# divchrono-master.net
KiCad netlist of a schematic drawn in EAGLE
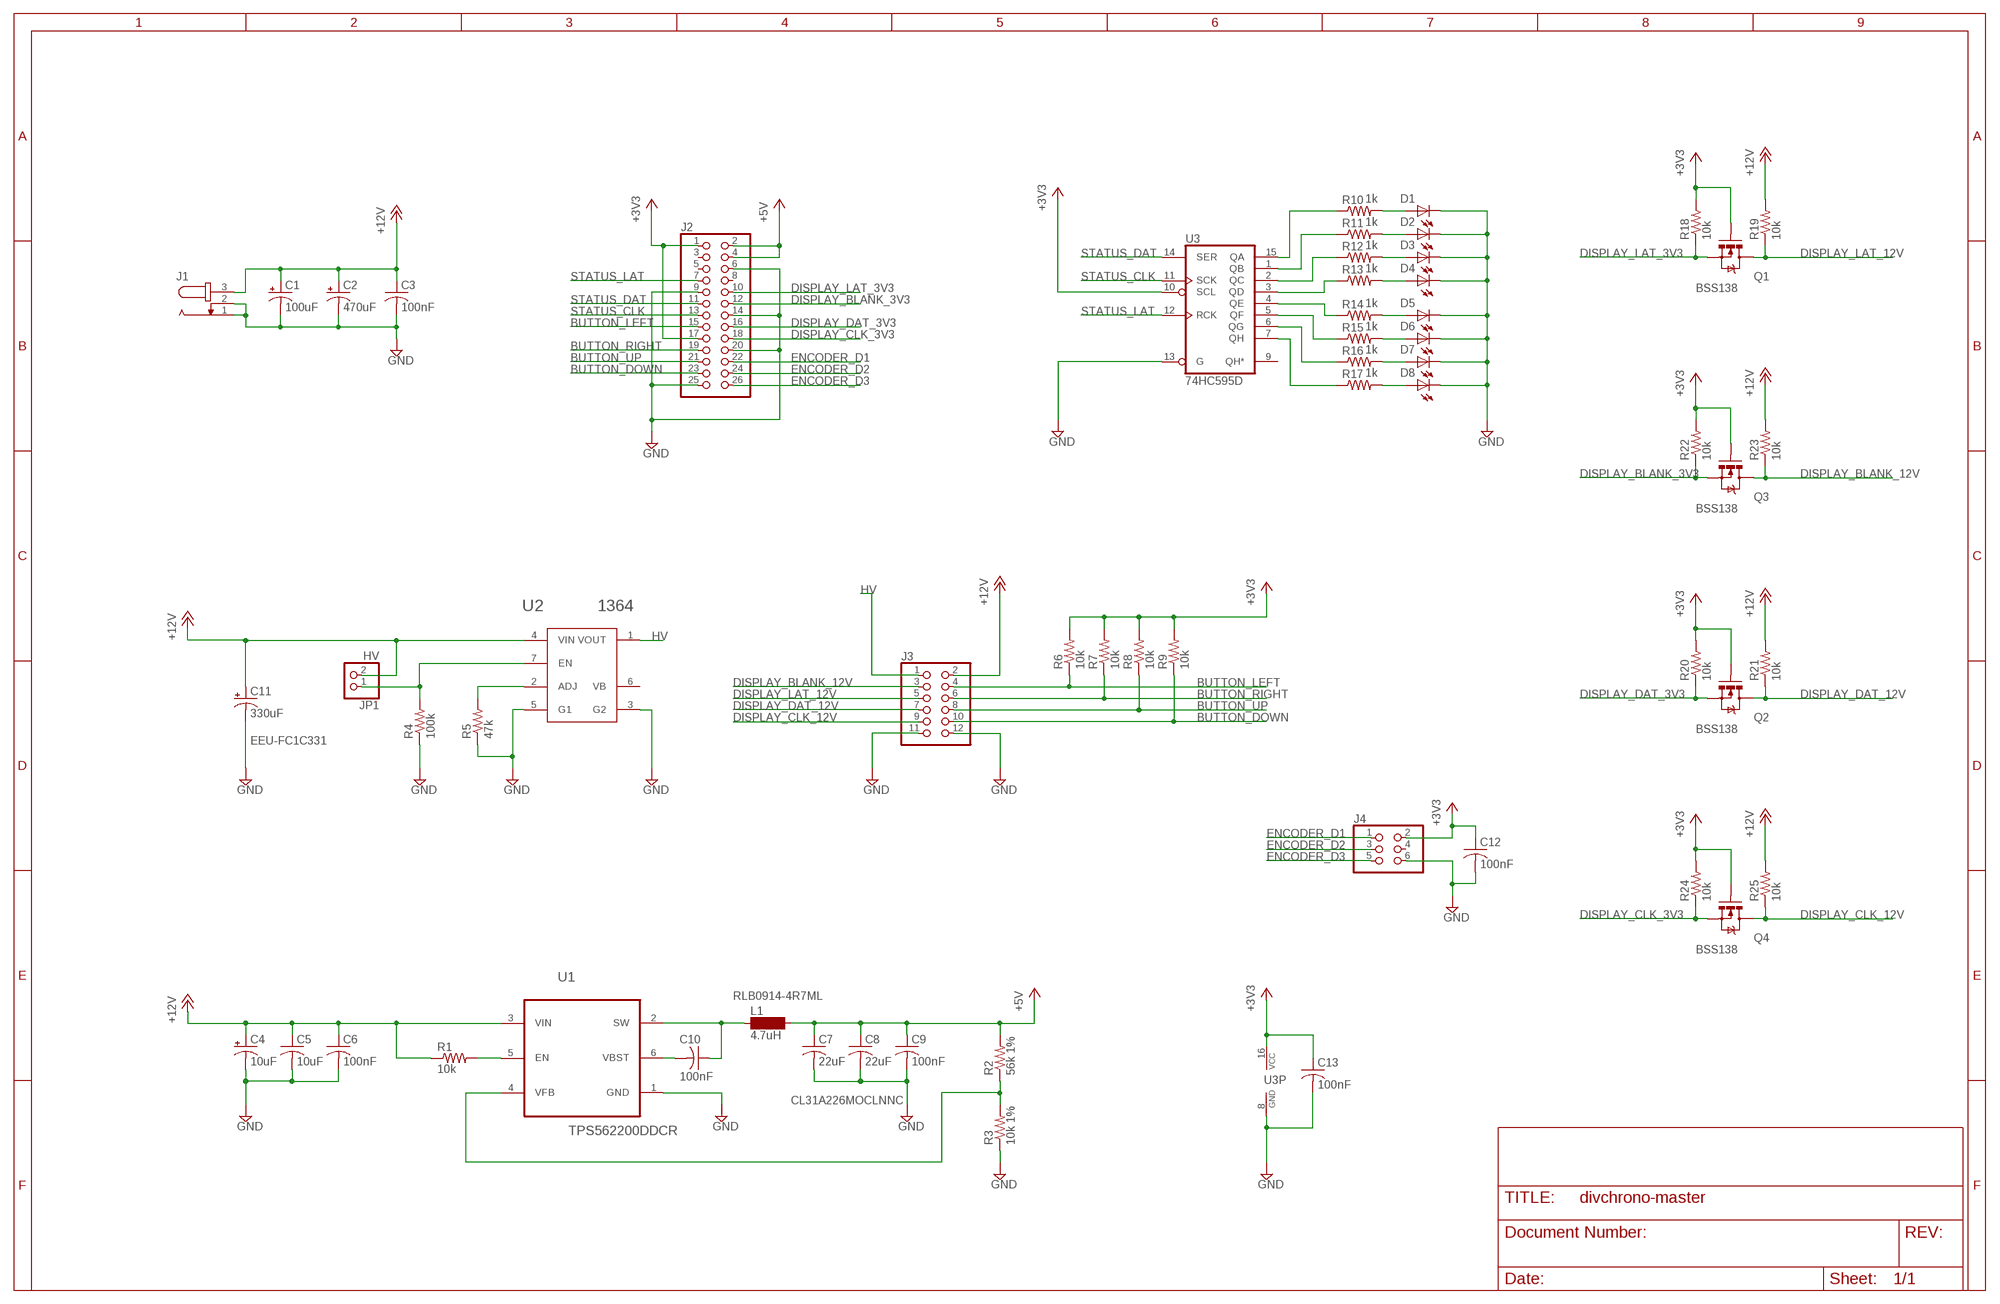
[diagram p0: schematic, sheet 1]

(export (version "E")
  (design (tool "Eeschema 10.0.6"))
  (components
    (comp (ref "C1")
      (value "100uF")
      (footprint "eagle-import:E2,5-6")
      (libsource (lib "eagle-import") (part "CPOL-USE2.5-6"))
    )
    (comp (ref "C2")
      (value "470uF")
      (footprint "eagle-import:E2,5-6")
      (libsource (lib "eagle-import") (part "CPOL-USE2.5-6"))
    )
    (comp (ref "C3")
      (value "100nF")
      (footprint "eagle-import:C1206")
      (libsource (lib "eagle-import") (part "C-USC1206"))
    )
    (comp (ref "C4")
      (value "10uF")
      (footprint "eagle-import:E2-5")
      (libsource (lib "eagle-import") (part "CPOL-USE2-5"))
    )
    (comp (ref "C5")
      (value "10uF")
      (footprint "eagle-import:C1206")
      (libsource (lib "eagle-import") (part "C-USC1206"))
    )
    (comp (ref "C6")
      (value "100nF")
      (footprint "eagle-import:C1206")
      (libsource (lib "eagle-import") (part "C-USC1206"))
    )
    (comp (ref "C7")
      (value "22uF")
      (footprint "eagle-import:C1206")
      (libsource (lib "eagle-import") (part "C-USC1206"))
    )
    (comp (ref "C8")
      (value "22uF")
      (footprint "eagle-import:C1206")
      (libsource (lib "eagle-import") (part "C-USC1206"))
    )
    (comp (ref "C9")
      (value "100nF")
      (footprint "eagle-import:C1206")
      (libsource (lib "eagle-import") (part "C-USC1206"))
    )
    (comp (ref "C10")
      (value "100nF")
      (footprint "eagle-import:C1206")
      (libsource (lib "eagle-import") (part "C-USC1206"))
    )
    (comp (ref "C11")
      (value "330uF")
      (footprint "eagle-import:E3,5-8")
      (libsource (lib "eagle-import") (part "CPOL-USE3.5-8"))
    )
    (comp (ref "C12")
      (value "100nF")
      (footprint "eagle-import:C1206")
      (libsource (lib "eagle-import") (part "C-USC1206"))
    )
    (comp (ref "C13")
      (value "100nF")
      (footprint "eagle-import:C1206")
      (libsource (lib "eagle-import") (part "C-USC1206"))
    )
    (comp (ref "D1")
      (value "LEDCHIPLED_1206")
      (footprint "eagle-import:CHIPLED_1206")
      (libsource (lib "eagle-import") (part "LEDCHIPLED_1206"))
    )
    (comp (ref "D2")
      (value "LEDCHIPLED_1206")
      (footprint "eagle-import:CHIPLED_1206")
      (libsource (lib "eagle-import") (part "LEDCHIPLED_1206"))
    )
    (comp (ref "D3")
      (value "LEDCHIPLED_1206")
      (footprint "eagle-import:CHIPLED_1206")
      (libsource (lib "eagle-import") (part "LEDCHIPLED_1206"))
    )
    (comp (ref "D4")
      (value "LEDCHIPLED_1206")
      (footprint "eagle-import:CHIPLED_1206")
      (libsource (lib "eagle-import") (part "LEDCHIPLED_1206"))
    )
    (comp (ref "D5")
      (value "LEDCHIPLED_1206")
      (footprint "eagle-import:CHIPLED_1206")
      (libsource (lib "eagle-import") (part "LEDCHIPLED_1206"))
    )
    (comp (ref "D6")
      (value "LEDCHIPLED_1206")
      (footprint "eagle-import:CHIPLED_1206")
      (libsource (lib "eagle-import") (part "LEDCHIPLED_1206"))
    )
    (comp (ref "D7")
      (value "LEDCHIPLED_1206")
      (footprint "eagle-import:CHIPLED_1206")
      (libsource (lib "eagle-import") (part "LEDCHIPLED_1206"))
    )
    (comp (ref "D8")
      (value "LEDCHIPLED_1206")
      (footprint "eagle-import:CHIPLED_1206")
      (libsource (lib "eagle-import") (part "LEDCHIPLED_1206"))
    )
    (comp (ref "J1")
      (value "JACK-PLUG0")
      (footprint "eagle-import:SPC4077")
      (libsource (lib "eagle-import") (part "JACK-PLUG0"))
    )
    (comp (ref "J2")
      (value "PINHD-2X13")
      (footprint "eagle-import:2X13")
      (libsource (lib "eagle-import") (part "PINHD-2X13"))
    )
    (comp (ref "J3")
      (value "PINHD-2X6")
      (footprint "eagle-import:2X06")
      (libsource (lib "eagle-import") (part "PINHD-2X6"))
    )
    (comp (ref "J4")
      (value "PINHD-2X3")
      (footprint "eagle-import:2X03")
      (libsource (lib "eagle-import") (part "PINHD-2X3"))
    )
    (comp (ref "JP1")
      (value "HV")
      (footprint "eagle-import:1X02")
      (libsource (lib "eagle-import") (part "PINHD-1X2"))
    )
    (comp (ref "L1")
      (value "4.7uH")
      (footprint "eagle-import:BS11")
      (libsource (lib "eagle-import") (part "BS11"))
    )
    (comp (ref "Q1")
      (value "BSS138")
      (footprint "eagle-import:SOT23-3")
      (libsource (lib "eagle-import") (part "MOSFET-NCHANNELBSS138"))
    )
    (comp (ref "Q2")
      (value "BSS138")
      (footprint "eagle-import:SOT23-3")
      (libsource (lib "eagle-import") (part "MOSFET-NCHANNELBSS138"))
    )
    (comp (ref "Q3")
      (value "BSS138")
      (footprint "eagle-import:SOT23-3")
      (libsource (lib "eagle-import") (part "MOSFET-NCHANNELBSS138"))
    )
    (comp (ref "Q4")
      (value "BSS138")
      (footprint "eagle-import:SOT23-3")
      (libsource (lib "eagle-import") (part "MOSFET-NCHANNELBSS138"))
    )
    (comp (ref "R1")
      (value "10k")
      (footprint "eagle-import:R1206")
      (libsource (lib "eagle-import") (part "R-US_R1206"))
    )
    (comp (ref "R2")
      (value "56k 1%")
      (footprint "eagle-import:R1206")
      (libsource (lib "eagle-import") (part "R-US_R1206"))
    )
    (comp (ref "R3")
      (value "10k 1%")
      (footprint "eagle-import:R1206")
      (libsource (lib "eagle-import") (part "R-US_R1206"))
    )
    (comp (ref "R4")
      (value "100k")
      (footprint "eagle-import:R1206")
      (libsource (lib "eagle-import") (part "R-US_R1206"))
    )
    (comp (ref "R5")
      (value "47k")
      (footprint "eagle-import:R1206")
      (libsource (lib "eagle-import") (part "R-US_R1206"))
    )
    (comp (ref "R6")
      (value "10k")
      (footprint "eagle-import:R1206")
      (libsource (lib "eagle-import") (part "R-US_R1206"))
    )
    (comp (ref "R7")
      (value "10k")
      (footprint "eagle-import:R1206")
      (libsource (lib "eagle-import") (part "R-US_R1206"))
    )
    (comp (ref "R8")
      (value "10k")
      (footprint "eagle-import:R1206")
      (libsource (lib "eagle-import") (part "R-US_R1206"))
    )
    (comp (ref "R9")
      (value "10k")
      (footprint "eagle-import:R1206")
      (libsource (lib "eagle-import") (part "R-US_R1206"))
    )
    (comp (ref "R10")
      (value "1k")
      (footprint "eagle-import:R1206")
      (libsource (lib "eagle-import") (part "R-US_R1206"))
    )
    (comp (ref "R11")
      (value "1k")
      (footprint "eagle-import:R1206")
      (libsource (lib "eagle-import") (part "R-US_R1206"))
    )
    (comp (ref "R12")
      (value "1k")
      (footprint "eagle-import:R1206")
      (libsource (lib "eagle-import") (part "R-US_R1206"))
    )
    (comp (ref "R13")
      (value "1k")
      (footprint "eagle-import:R1206")
      (libsource (lib "eagle-import") (part "R-US_R1206"))
    )
    (comp (ref "R14")
      (value "1k")
      (footprint "eagle-import:R1206")
      (libsource (lib "eagle-import") (part "R-US_R1206"))
    )
    (comp (ref "R15")
      (value "1k")
      (footprint "eagle-import:R1206")
      (libsource (lib "eagle-import") (part "R-US_R1206"))
    )
    (comp (ref "R16")
      (value "1k")
      (footprint "eagle-import:R1206")
      (libsource (lib "eagle-import") (part "R-US_R1206"))
    )
    (comp (ref "R17")
      (value "1k")
      (footprint "eagle-import:R1206")
      (libsource (lib "eagle-import") (part "R-US_R1206"))
    )
    (comp (ref "R18")
      (value "10k")
      (footprint "eagle-import:R1206")
      (libsource (lib "eagle-import") (part "R-US_R1206"))
    )
    (comp (ref "R19")
      (value "10k")
      (footprint "eagle-import:R1206")
      (libsource (lib "eagle-import") (part "R-US_R1206"))
    )
    (comp (ref "R20")
      (value "10k")
      (footprint "eagle-import:R1206")
      (libsource (lib "eagle-import") (part "R-US_R1206"))
    )
    (comp (ref "R21")
      (value "10k")
      (footprint "eagle-import:R1206")
      (libsource (lib "eagle-import") (part "R-US_R1206"))
    )
    (comp (ref "R22")
      (value "10k")
      (footprint "eagle-import:R1206")
      (libsource (lib "eagle-import") (part "R-US_R1206"))
    )
    (comp (ref "R23")
      (value "10k")
      (footprint "eagle-import:R1206")
      (libsource (lib "eagle-import") (part "R-US_R1206"))
    )
    (comp (ref "R24")
      (value "10k")
      (footprint "eagle-import:R1206")
      (libsource (lib "eagle-import") (part "R-US_R1206"))
    )
    (comp (ref "R25")
      (value "10k")
      (footprint "eagle-import:R1206")
      (libsource (lib "eagle-import") (part "R-US_R1206"))
    )
    (comp (ref "U1")
      (value "TPS562200DDCR")
      (footprint "eagle-import:SOT95P280X110-6N")
      (libsource (lib "eagle-import") (part "TPS562200DDCR"))
    )
    (comp (ref "U2")
      (value "1364")
      (footprint "eagle-import:1364")
      (libsource (lib "eagle-import") (part "1364"))
    )
    (comp (ref "U3")
      (value "74HC595D")
      (footprint "eagle-import:SO16")
      (libsource (lib "eagle-import") (part "74595DHC"))
    )
  )
  (nets
    (net (code "1") (name "+3V3") (class "Default")
      (node (ref "C12") (pin "1") (pinfunction "1_1") (pintype "passive"))
      (node (ref "C13") (pin "1") (pinfunction "1_1") (pintype "passive"))
      (node (ref "J2") (pin "1") (pinfunction "1_1") (pintype "passive"))
      (node (ref "J2") (pin "17") (pinfunction "17_17") (pintype "passive"))
      (node (ref "J4") (pin "2") (pinfunction "2_2") (pintype "passive"))
      (node (ref "Q1") (pin "1") (pinfunction "G_1") (pintype "passive"))
      (node (ref "Q2") (pin "1") (pinfunction "G_1") (pintype "passive"))
      (node (ref "Q3") (pin "1") (pinfunction "G_1") (pintype "passive"))
      (node (ref "Q4") (pin "1") (pinfunction "G_1") (pintype "passive"))
      (node (ref "R18") (pin "2") (pinfunction "2_2") (pintype "passive"))
      (node (ref "R20") (pin "2") (pinfunction "2_2") (pintype "passive"))
      (node (ref "R22") (pin "2") (pinfunction "2_2") (pintype "passive"))
      (node (ref "R24") (pin "2") (pinfunction "2_2") (pintype "passive"))
      (node (ref "R6") (pin "2") (pinfunction "2_2") (pintype "passive"))
      (node (ref "R7") (pin "2") (pinfunction "2_2") (pintype "passive"))
      (node (ref "R8") (pin "2") (pinfunction "2_2") (pintype "passive"))
      (node (ref "R9") (pin "2") (pinfunction "2_2") (pintype "passive"))
      (node (ref "U3") (pin "10") (pinfunction "SCL_10") (pintype "input"))
      (node (ref "U3") (pin "16") (pinfunction "VCC_16") (pintype "power_in"))
    )
    (net (code "2") (name "+5V") (class "Default")
      (node (ref "C7") (pin "1") (pinfunction "1_1") (pintype "passive"))
      (node (ref "C8") (pin "1") (pinfunction "1_1") (pintype "passive"))
      (node (ref "C9") (pin "1") (pinfunction "1_1") (pintype "passive"))
      (node (ref "J2") (pin "2") (pinfunction "2_2") (pintype "passive"))
      (node (ref "J2") (pin "4") (pinfunction "4_4") (pintype "passive"))
      (node (ref "L1") (pin "2") (pinfunction "2_2") (pintype "passive"))
      (node (ref "R2") (pin "2") (pinfunction "2_2") (pintype "passive"))
    )
    (net (code "3") (name "+12V") (class "Default")
      (node (ref "C1") (pin "+") (pinfunction "+_+") (pintype "passive"))
      (node (ref "C11") (pin "+") (pinfunction "+_+") (pintype "passive"))
      (node (ref "C2") (pin "+") (pinfunction "+_+") (pintype "passive"))
      (node (ref "C3") (pin "1") (pinfunction "1_1") (pintype "passive"))
      (node (ref "C4") (pin "+") (pinfunction "+_+") (pintype "passive"))
      (node (ref "C5") (pin "1") (pinfunction "1_1") (pintype "passive"))
      (node (ref "C6") (pin "1") (pinfunction "1_1") (pintype "passive"))
      (node (ref "J1") (pin "3") (pinfunction "3_3") (pintype "passive"))
      (node (ref "J3") (pin "2") (pinfunction "2_2") (pintype "passive"))
      (node (ref "JP1") (pin "2") (pinfunction "2_2") (pintype "passive"))
      (node (ref "R1") (pin "1") (pinfunction "1_1") (pintype "passive"))
      (node (ref "R19") (pin "2") (pinfunction "2_2") (pintype "passive"))
      (node (ref "R21") (pin "2") (pinfunction "2_2") (pintype "passive"))
      (node (ref "R23") (pin "2") (pinfunction "2_2") (pintype "passive"))
      (node (ref "R25") (pin "2") (pinfunction "2_2") (pintype "passive"))
      (node (ref "U1") (pin "3") (pinfunction "VIN_3") (pintype "power_in"))
      (node (ref "U2") (pin "4") (pinfunction "VIN_4") (pintype "passive"))
    )
    (net (code "4") (name "/BUTTON_DOWN") (class "Default")
      (node (ref "J2") (pin "23") (pinfunction "23_23") (pintype "passive"))
      (node (ref "J3") (pin "10") (pinfunction "10_10") (pintype "passive"))
      (node (ref "R9") (pin "1") (pinfunction "1_1") (pintype "passive"))
    )
    (net (code "5") (name "/BUTTON_LEFT") (class "Default")
      (node (ref "J2") (pin "15") (pinfunction "15_15") (pintype "passive"))
      (node (ref "J3") (pin "4") (pinfunction "4_4") (pintype "passive"))
      (node (ref "R6") (pin "1") (pinfunction "1_1") (pintype "passive"))
    )
    (net (code "6") (name "/BUTTON_RIGHT") (class "Default")
      (node (ref "J2") (pin "19") (pinfunction "19_19") (pintype "passive"))
      (node (ref "J3") (pin "6") (pinfunction "6_6") (pintype "passive"))
      (node (ref "R7") (pin "1") (pinfunction "1_1") (pintype "passive"))
    )
    (net (code "7") (name "/BUTTON_UP") (class "Default")
      (node (ref "J2") (pin "21") (pinfunction "21_21") (pintype "passive"))
      (node (ref "J3") (pin "8") (pinfunction "8_8") (pintype "passive"))
      (node (ref "R8") (pin "1") (pinfunction "1_1") (pintype "passive"))
    )
    (net (code "8") (name "/DISPLAY_BLANK_3V3") (class "Default")
      (node (ref "J2") (pin "12") (pinfunction "12_12") (pintype "passive"))
      (node (ref "Q3") (pin "2") (pinfunction "S_2") (pintype "passive"))
      (node (ref "R22") (pin "1") (pinfunction "1_1") (pintype "passive"))
    )
    (net (code "9") (name "/DISPLAY_BLANK_12V") (class "Default")
      (node (ref "J3") (pin "3") (pinfunction "3_3") (pintype "passive"))
      (node (ref "Q3") (pin "3") (pinfunction "D_3") (pintype "passive"))
      (node (ref "R23") (pin "1") (pinfunction "1_1") (pintype "passive"))
    )
    (net (code "10") (name "/DISPLAY_CLK_3V3") (class "Default")
      (node (ref "J2") (pin "18") (pinfunction "18_18") (pintype "passive"))
      (node (ref "Q4") (pin "2") (pinfunction "S_2") (pintype "passive"))
      (node (ref "R24") (pin "1") (pinfunction "1_1") (pintype "passive"))
    )
    (net (code "11") (name "/DISPLAY_CLK_12V") (class "Default")
      (node (ref "J3") (pin "9") (pinfunction "9_9") (pintype "passive"))
      (node (ref "Q4") (pin "3") (pinfunction "D_3") (pintype "passive"))
      (node (ref "R25") (pin "1") (pinfunction "1_1") (pintype "passive"))
    )
    (net (code "12") (name "/DISPLAY_DAT_3V3") (class "Default")
      (node (ref "J2") (pin "16") (pinfunction "16_16") (pintype "passive"))
      (node (ref "Q2") (pin "2") (pinfunction "S_2") (pintype "passive"))
      (node (ref "R20") (pin "1") (pinfunction "1_1") (pintype "passive"))
    )
    (net (code "13") (name "/DISPLAY_DAT_12V") (class "Default")
      (node (ref "J3") (pin "7") (pinfunction "7_7") (pintype "passive"))
      (node (ref "Q2") (pin "3") (pinfunction "D_3") (pintype "passive"))
      (node (ref "R21") (pin "1") (pinfunction "1_1") (pintype "passive"))
    )
    (net (code "14") (name "/DISPLAY_LAT_3V3") (class "Default")
      (node (ref "J2") (pin "10") (pinfunction "10_10") (pintype "passive"))
      (node (ref "Q1") (pin "2") (pinfunction "S_2") (pintype "passive"))
      (node (ref "R18") (pin "1") (pinfunction "1_1") (pintype "passive"))
    )
    (net (code "15") (name "/DISPLAY_LAT_12V") (class "Default")
      (node (ref "J3") (pin "5") (pinfunction "5_5") (pintype "passive"))
      (node (ref "Q1") (pin "3") (pinfunction "D_3") (pintype "passive"))
      (node (ref "R19") (pin "1") (pinfunction "1_1") (pintype "passive"))
    )
    (net (code "16") (name "/ENCODER_D1") (class "Default")
      (node (ref "J2") (pin "22") (pinfunction "22_22") (pintype "passive"))
      (node (ref "J4") (pin "1") (pinfunction "1_1") (pintype "passive"))
    )
    (net (code "17") (name "/ENCODER_D2") (class "Default")
      (node (ref "J2") (pin "24") (pinfunction "24_24") (pintype "passive"))
      (node (ref "J4") (pin "3") (pinfunction "3_3") (pintype "passive"))
    )
    (net (code "18") (name "/ENCODER_D3") (class "Default")
      (node (ref "J2") (pin "26") (pinfunction "26_26") (pintype "passive"))
      (node (ref "J4") (pin "5") (pinfunction "5_5") (pintype "passive"))
    )
    (net (code "19") (name "/HV") (class "Default")
      (node (ref "J3") (pin "1") (pinfunction "1_1") (pintype "passive"))
      (node (ref "U2") (pin "1") (pinfunction "VOUT_1") (pintype "passive"))
    )
    (net (code "20") (name "/STATUS_CLK") (class "Default")
      (node (ref "J2") (pin "13") (pinfunction "13_13") (pintype "passive"))
      (node (ref "U3") (pin "11") (pinfunction "SCK_11") (pintype "input"))
    )
    (net (code "21") (name "/STATUS_DAT") (class "Default")
      (node (ref "J2") (pin "11") (pinfunction "11_11") (pintype "passive"))
      (node (ref "U3") (pin "14") (pinfunction "SER_14") (pintype "input"))
    )
    (net (code "22") (name "/STATUS_LAT") (class "Default")
      (node (ref "J2") (pin "7") (pinfunction "7_7") (pintype "passive"))
      (node (ref "U3") (pin "12") (pinfunction "RCK_12") (pintype "input"))
    )
    (net (code "23") (name "GND") (class "Default")
      (node (ref "C1") (pin "-") (pinfunction "-_-") (pintype "passive"))
      (node (ref "C11") (pin "-") (pinfunction "-_-") (pintype "passive"))
      (node (ref "C12") (pin "2") (pinfunction "2_2") (pintype "passive"))
      (node (ref "C13") (pin "2") (pinfunction "2_2") (pintype "passive"))
      (node (ref "C2") (pin "-") (pinfunction "-_-") (pintype "passive"))
      (node (ref "C3") (pin "2") (pinfunction "2_2") (pintype "passive"))
      (node (ref "C4") (pin "-") (pinfunction "-_-") (pintype "passive"))
      (node (ref "C5") (pin "2") (pinfunction "2_2") (pintype "passive"))
      (node (ref "C6") (pin "2") (pinfunction "2_2") (pintype "passive"))
      (node (ref "C7") (pin "2") (pinfunction "2_2") (pintype "passive"))
      (node (ref "C8") (pin "2") (pinfunction "2_2") (pintype "passive"))
      (node (ref "C9") (pin "2") (pinfunction "2_2") (pintype "passive"))
      (node (ref "D1") (pin "C") (pinfunction "C_C") (pintype "passive"))
      (node (ref "D2") (pin "C") (pinfunction "C_C") (pintype "passive"))
      (node (ref "D3") (pin "C") (pinfunction "C_C") (pintype "passive"))
      (node (ref "D4") (pin "C") (pinfunction "C_C") (pintype "passive"))
      (node (ref "D5") (pin "C") (pinfunction "C_C") (pintype "passive"))
      (node (ref "D6") (pin "C") (pinfunction "C_C") (pintype "passive"))
      (node (ref "D7") (pin "C") (pinfunction "C_C") (pintype "passive"))
      (node (ref "D8") (pin "C") (pinfunction "C_C") (pintype "passive"))
      (node (ref "J1") (pin "1") (pinfunction "1_1") (pintype "passive"))
      (node (ref "J1") (pin "2") (pinfunction "2_2") (pintype "passive"))
      (node (ref "J2") (pin "14") (pinfunction "14_14") (pintype "passive"))
      (node (ref "J2") (pin "20") (pinfunction "20_20") (pintype "passive"))
      (node (ref "J2") (pin "25") (pinfunction "25_25") (pintype "passive"))
      (node (ref "J2") (pin "6") (pinfunction "6_6") (pintype "passive"))
      (node (ref "J2") (pin "9") (pinfunction "9_9") (pintype "passive"))
      (node (ref "J3") (pin "11") (pinfunction "11_11") (pintype "passive"))
      (node (ref "J3") (pin "12") (pinfunction "12_12") (pintype "passive"))
      (node (ref "J4") (pin "6") (pinfunction "6_6") (pintype "passive"))
      (node (ref "R3") (pin "1") (pinfunction "1_1") (pintype "passive"))
      (node (ref "R4") (pin "1") (pinfunction "1_1") (pintype "passive"))
      (node (ref "R5") (pin "1") (pinfunction "1_1") (pintype "passive"))
      (node (ref "U1") (pin "1") (pinfunction "GND_1") (pintype "passive"))
      (node (ref "U2") (pin "3") (pinfunction "G2_3") (pintype "passive"))
      (node (ref "U2") (pin "5") (pinfunction "G1_5") (pintype "passive"))
      (node (ref "U3") (pin "13") (pinfunction "G_13") (pintype "input"))
      (node (ref "U3") (pin "8") (pinfunction "GND_8") (pintype "power_in"))
    )
    (net (code "24") (name "Net-(D1-PadA)") (class "Default")
      (node (ref "D1") (pin "A") (pinfunction "A_A") (pintype "passive"))
      (node (ref "R10") (pin "2") (pinfunction "2_2") (pintype "passive"))
    )
    (net (code "25") (name "Net-(D2-PadA)") (class "Default")
      (node (ref "D2") (pin "A") (pinfunction "A_A") (pintype "passive"))
      (node (ref "R11") (pin "2") (pinfunction "2_2") (pintype "passive"))
    )
    (net (code "26") (name "Net-(D3-PadA)") (class "Default")
      (node (ref "D3") (pin "A") (pinfunction "A_A") (pintype "passive"))
      (node (ref "R12") (pin "2") (pinfunction "2_2") (pintype "passive"))
    )
    (net (code "27") (name "Net-(D4-PadA)") (class "Default")
      (node (ref "D4") (pin "A") (pinfunction "A_A") (pintype "passive"))
      (node (ref "R13") (pin "2") (pinfunction "2_2") (pintype "passive"))
    )
    (net (code "28") (name "Net-(D5-PadA)") (class "Default")
      (node (ref "D5") (pin "A") (pinfunction "A_A") (pintype "passive"))
      (node (ref "R14") (pin "2") (pinfunction "2_2") (pintype "passive"))
    )
    (net (code "29") (name "Net-(D6-PadA)") (class "Default")
      (node (ref "D6") (pin "A") (pinfunction "A_A") (pintype "passive"))
      (node (ref "R15") (pin "2") (pinfunction "2_2") (pintype "passive"))
    )
    (net (code "30") (name "Net-(D7-PadA)") (class "Default")
      (node (ref "D7") (pin "A") (pinfunction "A_A") (pintype "passive"))
      (node (ref "R16") (pin "2") (pinfunction "2_2") (pintype "passive"))
    )
    (net (code "31") (name "Net-(D8-PadA)") (class "Default")
      (node (ref "D8") (pin "A") (pinfunction "A_A") (pintype "passive"))
      (node (ref "R17") (pin "2") (pinfunction "2_2") (pintype "passive"))
    )
    (net (code "32") (name "Net-(U1-EN)") (class "Default")
      (node (ref "R1") (pin "2") (pinfunction "2_2") (pintype "passive"))
      (node (ref "U1") (pin "5") (pinfunction "EN_5") (pintype "input"))
    )
    (net (code "33") (name "Net-(U1-SW)") (class "Default")
      (node (ref "C10") (pin "1") (pinfunction "1_1") (pintype "passive"))
      (node (ref "L1") (pin "1") (pinfunction "1_1") (pintype "passive"))
      (node (ref "U1") (pin "2") (pinfunction "SW_2") (pintype "input"))
    )
    (net (code "34") (name "Net-(U1-VBST)") (class "Default")
      (node (ref "C10") (pin "2") (pinfunction "2_2") (pintype "passive"))
      (node (ref "U1") (pin "6") (pinfunction "VBST_6") (pintype "output"))
    )
    (net (code "35") (name "Net-(U1-VFB)") (class "Default")
      (node (ref "R2") (pin "1") (pinfunction "1_1") (pintype "passive"))
      (node (ref "R3") (pin "2") (pinfunction "2_2") (pintype "passive"))
      (node (ref "U1") (pin "4") (pinfunction "VFB_4") (pintype "input"))
    )
    (net (code "36") (name "Net-(U2-ADJ)") (class "Default")
      (node (ref "R5") (pin "2") (pinfunction "2_2") (pintype "passive"))
      (node (ref "U2") (pin "2") (pinfunction "ADJ_2") (pintype "passive"))
    )
    (net (code "37") (name "Net-(U2-EN)") (class "Default")
      (node (ref "JP1") (pin "1") (pinfunction "1_1") (pintype "passive"))
      (node (ref "R4") (pin "2") (pinfunction "2_2") (pintype "passive"))
      (node (ref "U2") (pin "7") (pinfunction "EN_7") (pintype "passive"))
    )
    (net (code "38") (name "Net-(U3A-QA)") (class "Default")
      (node (ref "R10") (pin "1") (pinfunction "1_1") (pintype "passive"))
      (node (ref "U3") (pin "15") (pinfunction "QA_15") (pintype "tri_state"))
    )
    (net (code "39") (name "Net-(U3A-QB)") (class "Default")
      (node (ref "R11") (pin "1") (pinfunction "1_1") (pintype "passive"))
      (node (ref "U3") (pin "1") (pinfunction "QB_1") (pintype "tri_state"))
    )
    (net (code "40") (name "Net-(U3A-QC)") (class "Default")
      (node (ref "R12") (pin "1") (pinfunction "1_1") (pintype "passive"))
      (node (ref "U3") (pin "2") (pinfunction "QC_2") (pintype "tri_state"))
    )
    (net (code "41") (name "Net-(U3A-QD)") (class "Default")
      (node (ref "R13") (pin "1") (pinfunction "1_1") (pintype "passive"))
      (node (ref "U3") (pin "3") (pinfunction "QD_3") (pintype "tri_state"))
    )
    (net (code "42") (name "Net-(U3A-QE)") (class "Default")
      (node (ref "R14") (pin "1") (pinfunction "1_1") (pintype "passive"))
      (node (ref "U3") (pin "4") (pinfunction "QE_4") (pintype "tri_state"))
    )
    (net (code "43") (name "Net-(U3A-QF)") (class "Default")
      (node (ref "R15") (pin "1") (pinfunction "1_1") (pintype "passive"))
      (node (ref "U3") (pin "5") (pinfunction "QF_5") (pintype "tri_state"))
    )
    (net (code "44") (name "Net-(U3A-QG)") (class "Default")
      (node (ref "R16") (pin "1") (pinfunction "1_1") (pintype "passive"))
      (node (ref "U3") (pin "6") (pinfunction "QG_6") (pintype "tri_state"))
    )
    (net (code "45") (name "Net-(U3A-QH)") (class "Default")
      (node (ref "R17") (pin "1") (pinfunction "1_1") (pintype "passive"))
      (node (ref "U3") (pin "7") (pinfunction "QH_7") (pintype "tri_state"))
    )
    (net (code "46") (name "unconnected-(J2-Pad3)") (class "Default")
      (node (ref "J2") (pin "3") (pinfunction "3_3") (pintype "passive"))
    )
    (net (code "47") (name "unconnected-(J2-Pad5)") (class "Default")
      (node (ref "J2") (pin "5") (pinfunction "5_5") (pintype "passive"))
    )
    (net (code "48") (name "unconnected-(J2-Pad8)") (class "Default")
      (node (ref "J2") (pin "8") (pinfunction "8_8") (pintype "passive"))
    )
    (net (code "49") (name "unconnected-(J4-Pad4)") (class "Default")
      (node (ref "J4") (pin "4") (pinfunction "4_4") (pintype "passive"))
    )
    (net (code "50") (name "unconnected-(U2-VB-Pad6)") (class "Default")
      (node (ref "U2") (pin "6") (pinfunction "VB_6") (pintype "passive"))
    )
    (net (code "51") (name "unconnected-(U3A-QH*-Pad9)") (class "Default")
      (node (ref "U3") (pin "9") (pinfunction "QH*_9") (pintype "tri_state"))
    )
  )
)
